# POWER.net
KiCad netlist of a schematic drawn in Altium Designer
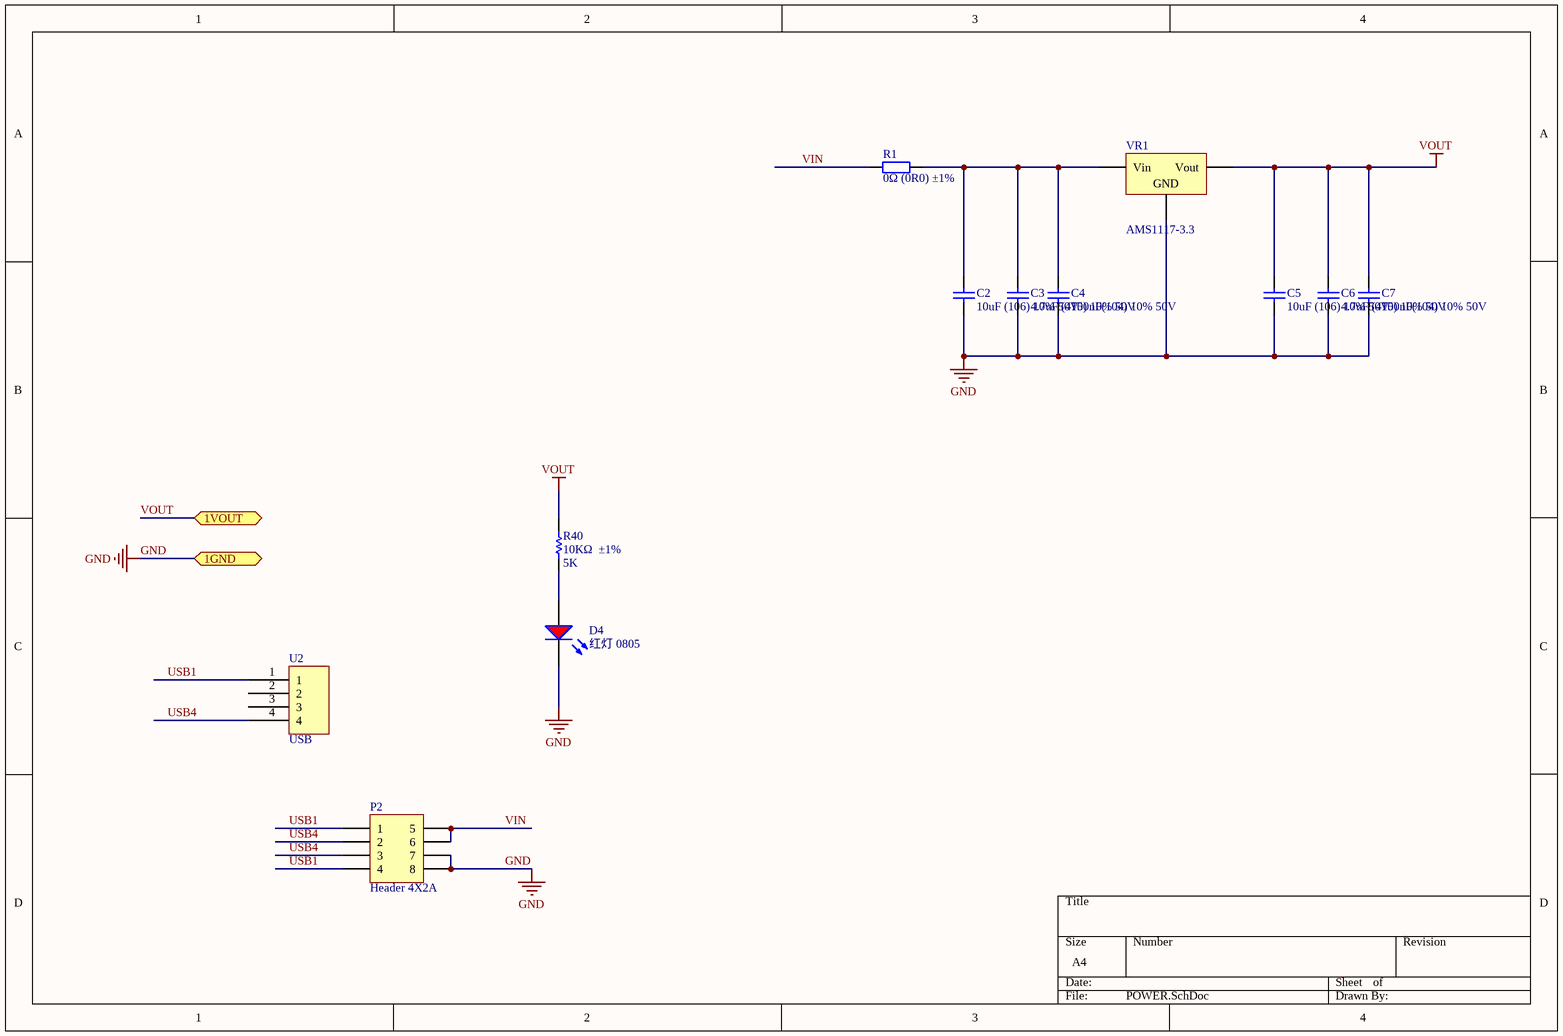
[diagram p0: POWER.SchDoc]

(export (version "E")
  (design (tool "Eeschema 10.0.6"))
  (components
    (comp (ref "C2")
      (value "10uF (106) 10% 50V")
      (footprint "1206_C")
      (description "贴片电容")
      (libsource (lib "Cap") (part "1206 10uF (106) 10% 50V"))
    )
    (comp (ref "C3")
      (value "4.7uF (475) 10% 50V")
      (footprint "1206_C")
      (description "贴片电容")
      (libsource (lib "Cap") (part "1206 4.7uF (475) 10% 50V"))
    )
    (comp (ref "C4")
      (value "100nF(104) 10% 50V")
      (footprint "0805_C")
      (description "贴片电容")
      (libsource (lib "Cap") (part "0805 100nF(104) 10% 50V"))
    )
    (comp (ref "C5")
      (value "10uF (106) 10% 50V")
      (footprint "1206_C")
      (description "贴片电容")
      (libsource (lib "Cap") (part "1206 10uF (106) 10% 50V"))
    )
    (comp (ref "C6")
      (value "4.7uF (475) 10% 50V")
      (footprint "1206_C")
      (description "贴片电容")
      (libsource (lib "Cap") (part "1206 4.7uF (475) 10% 50V"))
    )
    (comp (ref "C7")
      (value "100nF(104) 10% 50V")
      (footprint "0805_C")
      (description "贴片电容")
      (libsource (lib "Cap") (part "0805 100nF(104) 10% 50V"))
    )
    (comp (ref "D4")
      (value "红灯 0805")
      (footprint "0805_LED_S1")
      (description "发光二极管")
      (libsource (lib "Miscellaneous Devices LC") (part "0805 红灯"))
    )
    (comp (ref "P2")
      (value "Header 4X2A")
      (footprint "HDR2X4_CEN")
      (description "Header, 4-Pin, Dual row")
      (fields (field (name "PUBLISHER") "Altium Limited"))
      (libsource (lib "Miscellaneous Connectors") (part "Header 4X2A"))
    )
    (comp (ref "R1")
      (value "0Ω (0R0) ±1%")
      (footprint "1206_R")
      (description "贴片电阻")
      (libsource (lib "RES") (part "1206 0Ω (0R0) 1%"))
    )
    (comp (ref "R40")
      (value "10KΩ  ±1%")
      (footprint "0805_R")
      (description "Resistor")
      (fields (field (name "ALTIUM_VALUE") "5K") (field (name "PUBLISHER") "Altium Limited"))
      (libsource (lib "Miscellaneous Devices") (part "Res1"))
    )
    (comp (ref "U2") (value "USB") (footprint "USB_PORT") (libsource (lib "LS_Schlib1") (part "USB")))
    (comp (ref "VR1")
      (value "AMS1117-3.3")
      (footprint "SOT-223")
      (description "低压差线性稳压(LDO)")
      (libsource (lib "LDO") (part "SOT-223 AMS1117-3.3"))
    )
  )
  (nets
    (net (code "1") (name "/USB1") (class "Default")
      (node (ref "P2") (pin "1") (pinfunction "1_1") (pintype "passive"))
      (node (ref "P2") (pin "4") (pinfunction "4_4") (pintype "passive"))
      (node (ref "U2") (pin "1") (pinfunction "1_1") (pintype "passive"))
    )
    (net (code "2") (name "/USB4") (class "Default")
      (node (ref "P2") (pin "2") (pinfunction "2_2") (pintype "passive"))
      (node (ref "P2") (pin "3") (pinfunction "3_3") (pintype "passive"))
      (node (ref "U2") (pin "4") (pinfunction "4_4") (pintype "passive"))
    )
    (net (code "3") (name "/VIN") (class "Default")
      (node (ref "P2") (pin "5") (pinfunction "5_5") (pintype "passive"))
      (node (ref "P2") (pin "6") (pinfunction "6_6") (pintype "passive"))
      (node (ref "R1") (pin "1") (pinfunction "1_1") (pintype "passive"))
    )
    (net (code "4") (name "GND") (class "Default")
      (node (ref "C2") (pin "1") (pinfunction "1_1") (pintype "passive"))
      (node (ref "C3") (pin "1") (pinfunction "1_1") (pintype "passive"))
      (node (ref "C4") (pin "1") (pinfunction "1_1") (pintype "passive"))
      (node (ref "C5") (pin "1") (pinfunction "1_1") (pintype "passive"))
      (node (ref "C6") (pin "1") (pinfunction "1_1") (pintype "passive"))
      (node (ref "C7") (pin "1") (pinfunction "1_1") (pintype "passive"))
      (node (ref "D4") (pin "K") (pinfunction "K_K") (pintype "passive"))
      (node (ref "P2") (pin "7") (pinfunction "7_7") (pintype "passive"))
      (node (ref "P2") (pin "8") (pinfunction "8_8") (pintype "passive"))
      (node (ref "VR1") (pin "1") (pinfunction "GND_1") (pintype "passive"))
    )
    (net (code "5") (name "Net-(D4-PadA)") (class "Default")
      (node (ref "D4") (pin "A") (pinfunction "A_A") (pintype "passive"))
      (node (ref "R40") (pin "1") (pinfunction "1_1") (pintype "passive"))
    )
    (net (code "6") (name "Net-(VR1-Vin)") (class "Default")
      (node (ref "C2") (pin "2") (pinfunction "2_2") (pintype "passive"))
      (node (ref "C3") (pin "2") (pinfunction "2_2") (pintype "passive"))
      (node (ref "C4") (pin "2") (pinfunction "2_2") (pintype "passive"))
      (node (ref "R1") (pin "2") (pinfunction "2_2") (pintype "passive"))
      (node (ref "VR1") (pin "3") (pinfunction "Vin_3") (pintype "passive"))
    )
    (net (code "7") (name "VOUT") (class "Default")
      (node (ref "C5") (pin "2") (pinfunction "2_2") (pintype "passive"))
      (node (ref "C6") (pin "2") (pinfunction "2_2") (pintype "passive"))
      (node (ref "C7") (pin "2") (pinfunction "2_2") (pintype "passive"))
      (node (ref "R40") (pin "2") (pinfunction "2_2") (pintype "passive"))
      (node (ref "VR1") (pin "2") (pinfunction "Vout_2") (pintype "passive"))
    )
    (net (code "8") (name "unconnected-(U2-Pad2)") (class "Default")
      (node (ref "U2") (pin "2") (pinfunction "2_2") (pintype "passive"))
    )
    (net (code "9") (name "unconnected-(U2-Pad3)") (class "Default")
      (node (ref "U2") (pin "3") (pinfunction "3_3") (pintype "passive"))
    )
  )
)
